# emmc.net
KiCad netlist of a schematic drawn in Altium Designer
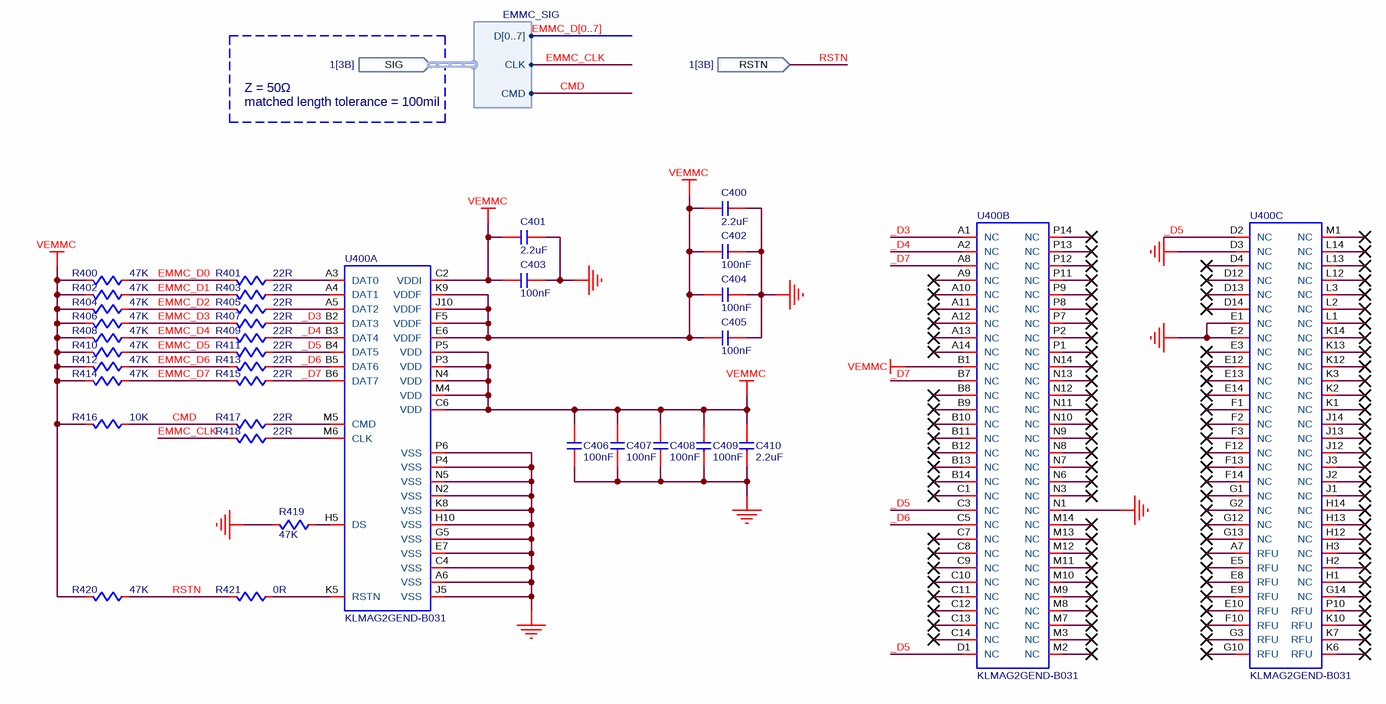
[diagram p0: emmc.schdoc]

(export (version "E")
  (design (tool "Eeschema 10.0.6"))
  (components
    (comp (ref "C400")
      (value "2.2uF")
      (footprint "mw:C0402")
      (fields (field (name "VOLTAGE") "25V") (field (name "Comment") "C-NOMO"))
      (libsource (lib "mw") (part "C-NOMO"))
    )
    (comp (ref "C401")
      (value "2.2uF")
      (footprint "mw:C0402")
      (fields (field (name "VOLTAGE") "25V") (field (name "Comment") "C-NOMO"))
      (libsource (lib "mw") (part "C-NOMO"))
    )
    (comp (ref "C402")
      (value "100nF")
      (footprint "mw:C0402")
      (fields (field (name "VOLTAGE") "25V") (field (name "Comment") "C-NOMO"))
      (libsource (lib "mw") (part "C-NOMO"))
    )
    (comp (ref "C403")
      (value "100nF")
      (footprint "mw:C0402")
      (fields (field (name "VOLTAGE") "25V") (field (name "Comment") "C-NOMO"))
      (libsource (lib "mw") (part "C-NOMO"))
    )
    (comp (ref "C404")
      (value "100nF")
      (footprint "mw:C0402")
      (fields (field (name "VOLTAGE") "25V") (field (name "Comment") "C-NOMO"))
      (libsource (lib "mw") (part "C-NOMO"))
    )
    (comp (ref "C405")
      (value "100nF")
      (footprint "mw:C0402")
      (fields (field (name "VOLTAGE") "25V") (field (name "Comment") "C-NOMO"))
      (libsource (lib "mw") (part "C-NOMO"))
    )
    (comp (ref "C406")
      (value "100nF")
      (footprint "mw:C0402")
      (fields (field (name "VOLTAGE") "25V") (field (name "Comment") "C-NOMO"))
      (libsource (lib "mw") (part "C-NOMO"))
    )
    (comp (ref "C407")
      (value "100nF")
      (footprint "mw:C0402")
      (fields (field (name "VOLTAGE") "25V") (field (name "Comment") "C-NOMO"))
      (libsource (lib "mw") (part "C-NOMO"))
    )
    (comp (ref "C408")
      (value "100nF")
      (footprint "mw:C0402")
      (fields (field (name "VOLTAGE") "25V") (field (name "Comment") "C-NOMO"))
      (libsource (lib "mw") (part "C-NOMO"))
    )
    (comp (ref "C409")
      (value "100nF")
      (footprint "mw:C0402")
      (fields (field (name "VOLTAGE") "25V") (field (name "Comment") "C-NOMO"))
      (libsource (lib "mw") (part "C-NOMO"))
    )
    (comp (ref "C410")
      (value "2.2uF")
      (footprint "mw:C0402")
      (fields (field (name "VOLTAGE") "25V") (field (name "Comment") "C-NOMO"))
      (libsource (lib "mw") (part "C-NOMO"))
    )
    (comp (ref "R400")
      (value "47K")
      (footprint "mw:R0402")
      (fields (field (name "Comment") "R"))
      (libsource (lib "mw") (part "R"))
    )
    (comp (ref "R401")
      (value "22R")
      (footprint "mw:R0402")
      (fields (field (name "Comment") "R"))
      (libsource (lib "mw") (part "R"))
    )
    (comp (ref "R402")
      (value "47K")
      (footprint "mw:R0402")
      (fields (field (name "Comment") "R"))
      (libsource (lib "mw") (part "R"))
    )
    (comp (ref "R403")
      (value "22R")
      (footprint "mw:R0402")
      (fields (field (name "Comment") "R"))
      (libsource (lib "mw") (part "R"))
    )
    (comp (ref "R404")
      (value "47K")
      (footprint "mw:R0402")
      (fields (field (name "Comment") "R"))
      (libsource (lib "mw") (part "R"))
    )
    (comp (ref "R405")
      (value "22R")
      (footprint "mw:R0402")
      (fields (field (name "Comment") "R"))
      (libsource (lib "mw") (part "R"))
    )
    (comp (ref "R406")
      (value "47K")
      (footprint "mw:R0402")
      (fields (field (name "Comment") "R"))
      (libsource (lib "mw") (part "R"))
    )
    (comp (ref "R407")
      (value "22R")
      (footprint "mw:R0402")
      (fields (field (name "Comment") "R"))
      (libsource (lib "mw") (part "R"))
    )
    (comp (ref "R408")
      (value "47K")
      (footprint "mw:R0402")
      (fields (field (name "Comment") "R"))
      (libsource (lib "mw") (part "R"))
    )
    (comp (ref "R409")
      (value "22R")
      (footprint "mw:R0402")
      (fields (field (name "Comment") "R"))
      (libsource (lib "mw") (part "R"))
    )
    (comp (ref "R410")
      (value "47K")
      (footprint "mw:R0402")
      (fields (field (name "Comment") "R"))
      (libsource (lib "mw") (part "R"))
    )
    (comp (ref "R411")
      (value "22R")
      (footprint "mw:R0402")
      (fields (field (name "Comment") "R"))
      (libsource (lib "mw") (part "R"))
    )
    (comp (ref "R412")
      (value "47K")
      (footprint "mw:R0402")
      (fields (field (name "Comment") "R"))
      (libsource (lib "mw") (part "R"))
    )
    (comp (ref "R413")
      (value "22R")
      (footprint "mw:R0402")
      (fields (field (name "Comment") "R"))
      (libsource (lib "mw") (part "R"))
    )
    (comp (ref "R414")
      (value "47K")
      (footprint "mw:R0402")
      (fields (field (name "Comment") "R"))
      (libsource (lib "mw") (part "R"))
    )
    (comp (ref "R415")
      (value "22R")
      (footprint "mw:R0402")
      (fields (field (name "Comment") "R"))
      (libsource (lib "mw") (part "R"))
    )
    (comp (ref "R416")
      (value "10K")
      (footprint "mw:R0402")
      (fields (field (name "Comment") "R"))
      (libsource (lib "mw") (part "R"))
    )
    (comp (ref "R417")
      (value "22R")
      (footprint "mw:R0402")
      (fields (field (name "Comment") "R"))
      (libsource (lib "mw") (part "R"))
    )
    (comp (ref "R418")
      (value "22R")
      (footprint "mw:R0402")
      (fields (field (name "Comment") "R"))
      (libsource (lib "mw") (part "R"))
    )
    (comp (ref "R419")
      (value "47K")
      (footprint "mw:R0402")
      (fields (field (name "Comment") "R"))
      (libsource (lib "mw") (part "R"))
    )
    (comp (ref "R420")
      (value "47K")
      (footprint "mw:R0402")
      (fields (field (name "Comment") "R"))
      (libsource (lib "mw") (part "R"))
    )
    (comp (ref "R421")
      (value "0R")
      (footprint "mw:R0402")
      (fields (field (name "Comment") "R"))
      (libsource (lib "mw") (part "R"))
    )
    (comp (ref "U400")
      (value "KLMAG2GEND-B031")
      (footprint "mw:KLMAG2GEND-B031")
      (description "EMMC")
      (libsource (lib "mw") (part "KLMAG2GEND-B031"))
    )
  )
  (nets
    (net (code "2") (name "/CMD") (class "Default")
      (node (ref "R416") (pin "2") (pinfunction "2_2") (pintype "passive"))
      (node (ref "R417") (pin "1") (pinfunction "1_1") (pintype "passive"))
    )
    (net (code "3") (name "/EMMC_CLK") (class "Default")
      (node (ref "R418") (pin "1") (pinfunction "1_1") (pintype "passive"))
    )
    (net (code "4") (name "/EMMC_D0") (class "Default")
      (node (ref "R400") (pin "2") (pinfunction "2_2") (pintype "passive"))
      (node (ref "R401") (pin "1") (pinfunction "1_1") (pintype "passive"))
    )
    (net (code "5") (name "/EMMC_D1") (class "Default")
      (node (ref "R402") (pin "2") (pinfunction "2_2") (pintype "passive"))
      (node (ref "R403") (pin "1") (pinfunction "1_1") (pintype "passive"))
    )
    (net (code "6") (name "/EMMC_D2") (class "Default")
      (node (ref "R404") (pin "2") (pinfunction "2_2") (pintype "passive"))
      (node (ref "R405") (pin "1") (pinfunction "1_1") (pintype "passive"))
    )
    (net (code "7") (name "/EMMC_D3") (class "Default")
      (node (ref "R406") (pin "2") (pinfunction "2_2") (pintype "passive"))
      (node (ref "R407") (pin "1") (pinfunction "1_1") (pintype "passive"))
    )
    (net (code "8") (name "/EMMC_D4") (class "Default")
      (node (ref "R408") (pin "2") (pinfunction "2_2") (pintype "passive"))
      (node (ref "R409") (pin "1") (pinfunction "1_1") (pintype "passive"))
    )
    (net (code "9") (name "/EMMC_D5") (class "Default")
      (node (ref "R410") (pin "2") (pinfunction "2_2") (pintype "passive"))
      (node (ref "R411") (pin "1") (pinfunction "1_1") (pintype "passive"))
    )
    (net (code "10") (name "/EMMC_D6") (class "Default")
      (node (ref "R412") (pin "2") (pinfunction "2_2") (pintype "passive"))
      (node (ref "R413") (pin "1") (pinfunction "1_1") (pintype "passive"))
    )
    (net (code "11") (name "/EMMC_D7") (class "Default")
      (node (ref "R414") (pin "2") (pinfunction "2_2") (pintype "passive"))
      (node (ref "R415") (pin "1") (pinfunction "1_1") (pintype "passive"))
    )
    (net (code "13") (name "/RSTN") (class "Default")
      (node (ref "R420") (pin "2") (pinfunction "2_2") (pintype "passive"))
      (node (ref "R421") (pin "1") (pinfunction "1_1") (pintype "passive"))
    )
    (net (code "14") (name "/_D3") (class "Default")
      (node (ref "R407") (pin "2") (pinfunction "2_2") (pintype "passive"))
      (node (ref "U400") (pin "A1") (pinfunction "NC_A1") (pintype "passive"))
      (node (ref "U400") (pin "B2") (pinfunction "DAT3_B2") (pintype "passive"))
    )
    (net (code "15") (name "/_D4") (class "Default")
      (node (ref "R409") (pin "2") (pinfunction "2_2") (pintype "passive"))
      (node (ref "U400") (pin "A2") (pinfunction "NC_A2") (pintype "passive"))
      (node (ref "U400") (pin "B3") (pinfunction "DAT4_B3") (pintype "passive"))
    )
    (net (code "16") (name "/_D5") (class "Default")
      (node (ref "R411") (pin "2") (pinfunction "2_2") (pintype "passive"))
      (node (ref "U400") (pin "B4") (pinfunction "DAT5_B4") (pintype "passive"))
      (node (ref "U400") (pin "C3") (pinfunction "NC_C3") (pintype "passive"))
      (node (ref "U400") (pin "D1") (pinfunction "NC_D1") (pintype "passive"))
      (node (ref "U400") (pin "D2") (pinfunction "NC_D2") (pintype "passive"))
    )
    (net (code "17") (name "/_D6") (class "Default")
      (node (ref "R413") (pin "2") (pinfunction "2_2") (pintype "passive"))
      (node (ref "U400") (pin "B5") (pinfunction "DAT6_B5") (pintype "passive"))
      (node (ref "U400") (pin "C5") (pinfunction "NC_C5") (pintype "passive"))
    )
    (net (code "18") (name "/_D7") (class "Default")
      (node (ref "R415") (pin "2") (pinfunction "2_2") (pintype "passive"))
      (node (ref "U400") (pin "A8") (pinfunction "NC_A8") (pintype "passive"))
      (node (ref "U400") (pin "B6") (pinfunction "DAT7_B6") (pintype "passive"))
      (node (ref "U400") (pin "B7") (pinfunction "NC_B7") (pintype "passive"))
    )
    (net (code "20") (name "GND") (class "Default")
      (node (ref "C400") (pin "1") (pinfunction "1_1") (pintype "passive"))
      (node (ref "C401") (pin "1") (pinfunction "1_1") (pintype "passive"))
      (node (ref "C402") (pin "1") (pinfunction "1_1") (pintype "passive"))
      (node (ref "C403") (pin "1") (pinfunction "1_1") (pintype "passive"))
      (node (ref "C404") (pin "1") (pinfunction "1_1") (pintype "passive"))
      (node (ref "C405") (pin "1") (pinfunction "1_1") (pintype "passive"))
      (node (ref "C406") (pin "1") (pinfunction "1_1") (pintype "passive"))
      (node (ref "C407") (pin "1") (pinfunction "1_1") (pintype "passive"))
      (node (ref "C408") (pin "1") (pinfunction "1_1") (pintype "passive"))
      (node (ref "C409") (pin "1") (pinfunction "1_1") (pintype "passive"))
      (node (ref "C410") (pin "1") (pinfunction "1_1") (pintype "passive"))
      (node (ref "R419") (pin "1") (pinfunction "1_1") (pintype "passive"))
      (node (ref "U400") (pin "A6") (pinfunction "VSS_A6") (pintype "passive"))
      (node (ref "U400") (pin "C4") (pinfunction "VSS_C4") (pintype "passive"))
      (node (ref "U400") (pin "D3") (pinfunction "NC_D3") (pintype "passive"))
      (node (ref "U400") (pin "E1") (pinfunction "NC_E1") (pintype "passive"))
      (node (ref "U400") (pin "E2") (pinfunction "NC_E2") (pintype "passive"))
      (node (ref "U400") (pin "E7") (pinfunction "VSS_E7") (pintype "passive"))
      (node (ref "U400") (pin "G5") (pinfunction "VSS_G5") (pintype "passive"))
      (node (ref "U400") (pin "H10") (pinfunction "VSS_H10") (pintype "passive"))
      (node (ref "U400") (pin "J5") (pinfunction "VSS_J5") (pintype "passive"))
      (node (ref "U400") (pin "K8") (pinfunction "VSS_K8") (pintype "passive"))
      (node (ref "U400") (pin "N1") (pinfunction "NC_N1") (pintype "passive"))
      (node (ref "U400") (pin "N2") (pinfunction "VSS_N2") (pintype "passive"))
      (node (ref "U400") (pin "N5") (pinfunction "VSS_N5") (pintype "passive"))
      (node (ref "U400") (pin "P4") (pinfunction "VSS_P4") (pintype "passive"))
      (node (ref "U400") (pin "P6") (pinfunction "VSS_P6") (pintype "passive"))
    )
    (net (code "21") (name "Net-(U400A-CLK)") (class "Default")
      (node (ref "R418") (pin "2") (pinfunction "2_2") (pintype "passive"))
      (node (ref "U400") (pin "M6") (pinfunction "CLK_M6") (pintype "passive"))
    )
    (net (code "22") (name "Net-(U400A-CMD)") (class "Default")
      (node (ref "R417") (pin "2") (pinfunction "2_2") (pintype "passive"))
      (node (ref "U400") (pin "M5") (pinfunction "CMD_M5") (pintype "passive"))
    )
    (net (code "23") (name "Net-(U400A-DAT0)") (class "Default")
      (node (ref "R401") (pin "2") (pinfunction "2_2") (pintype "passive"))
      (node (ref "U400") (pin "A3") (pinfunction "DAT0_A3") (pintype "passive"))
    )
    (net (code "24") (name "Net-(U400A-DAT1)") (class "Default")
      (node (ref "R403") (pin "2") (pinfunction "2_2") (pintype "passive"))
      (node (ref "U400") (pin "A4") (pinfunction "DAT1_A4") (pintype "passive"))
    )
    (net (code "25") (name "Net-(U400A-DAT2)") (class "Default")
      (node (ref "R405") (pin "2") (pinfunction "2_2") (pintype "passive"))
      (node (ref "U400") (pin "A5") (pinfunction "DAT2_A5") (pintype "passive"))
    )
    (net (code "26") (name "Net-(U400A-DS)") (class "Default")
      (node (ref "R419") (pin "2") (pinfunction "2_2") (pintype "passive"))
      (node (ref "U400") (pin "H5") (pinfunction "DS_H5") (pintype "passive"))
    )
    (net (code "27") (name "Net-(U400A-RSTN)") (class "Default")
      (node (ref "R421") (pin "2") (pinfunction "2_2") (pintype "passive"))
      (node (ref "U400") (pin "K5") (pinfunction "RSTN_K5") (pintype "passive"))
    )
    (net (code "28") (name "VEMMC") (class "Default")
      (node (ref "C400") (pin "2") (pinfunction "2_2") (pintype "passive"))
      (node (ref "C401") (pin "2") (pinfunction "2_2") (pintype "passive"))
      (node (ref "C402") (pin "2") (pinfunction "2_2") (pintype "passive"))
      (node (ref "C403") (pin "2") (pinfunction "2_2") (pintype "passive"))
      (node (ref "C404") (pin "2") (pinfunction "2_2") (pintype "passive"))
      (node (ref "C405") (pin "2") (pinfunction "2_2") (pintype "passive"))
      (node (ref "C406") (pin "2") (pinfunction "2_2") (pintype "passive"))
      (node (ref "C407") (pin "2") (pinfunction "2_2") (pintype "passive"))
      (node (ref "C408") (pin "2") (pinfunction "2_2") (pintype "passive"))
      (node (ref "C409") (pin "2") (pinfunction "2_2") (pintype "passive"))
      (node (ref "C410") (pin "2") (pinfunction "2_2") (pintype "passive"))
      (node (ref "R400") (pin "1") (pinfunction "1_1") (pintype "passive"))
      (node (ref "R402") (pin "1") (pinfunction "1_1") (pintype "passive"))
      (node (ref "R404") (pin "1") (pinfunction "1_1") (pintype "passive"))
      (node (ref "R406") (pin "1") (pinfunction "1_1") (pintype "passive"))
      (node (ref "R408") (pin "1") (pinfunction "1_1") (pintype "passive"))
      (node (ref "R410") (pin "1") (pinfunction "1_1") (pintype "passive"))
      (node (ref "R412") (pin "1") (pinfunction "1_1") (pintype "passive"))
      (node (ref "R414") (pin "1") (pinfunction "1_1") (pintype "passive"))
      (node (ref "R416") (pin "1") (pinfunction "1_1") (pintype "passive"))
      (node (ref "R420") (pin "1") (pinfunction "1_1") (pintype "passive"))
      (node (ref "U400") (pin "B1") (pinfunction "NC_B1") (pintype "passive"))
      (node (ref "U400") (pin "C2") (pinfunction "VDDI_C2") (pintype "passive"))
      (node (ref "U400") (pin "C6") (pinfunction "VDD_C6") (pintype "passive"))
      (node (ref "U400") (pin "E6") (pinfunction "VDDF_E6") (pintype "passive"))
      (node (ref "U400") (pin "F5") (pinfunction "VDDF_F5") (pintype "passive"))
      (node (ref "U400") (pin "J10") (pinfunction "VDDF_J10") (pintype "passive"))
      (node (ref "U400") (pin "K9") (pinfunction "VDDF_K9") (pintype "passive"))
      (node (ref "U400") (pin "M4") (pinfunction "VDD_M4") (pintype "passive"))
      (node (ref "U400") (pin "N4") (pinfunction "VDD_N4") (pintype "passive"))
      (node (ref "U400") (pin "P3") (pinfunction "VDD_P3") (pintype "passive"))
      (node (ref "U400") (pin "P5") (pinfunction "VDD_P5") (pintype "passive"))
    )
    (net (code "29") (name "unconnected-(U400B-NC-PadA9)") (class "Default")
      (node (ref "U400") (pin "A9") (pinfunction "NC_A9") (pintype "passive+no_connect"))
    )
    (net (code "30") (name "unconnected-(U400B-NC-PadA10)") (class "Default")
      (node (ref "U400") (pin "A10") (pinfunction "NC_A10") (pintype "passive+no_connect"))
    )
    (net (code "31") (name "unconnected-(U400B-NC-PadA11)") (class "Default")
      (node (ref "U400") (pin "A11") (pinfunction "NC_A11") (pintype "passive+no_connect"))
    )
    (net (code "32") (name "unconnected-(U400B-NC-PadA12)") (class "Default")
      (node (ref "U400") (pin "A12") (pinfunction "NC_A12") (pintype "passive+no_connect"))
    )
    (net (code "33") (name "unconnected-(U400B-NC-PadA13)") (class "Default")
      (node (ref "U400") (pin "A13") (pinfunction "NC_A13") (pintype "passive+no_connect"))
    )
    (net (code "34") (name "unconnected-(U400B-NC-PadA14)") (class "Default")
      (node (ref "U400") (pin "A14") (pinfunction "NC_A14") (pintype "passive+no_connect"))
    )
    (net (code "35") (name "unconnected-(U400B-NC-PadB8)") (class "Default")
      (node (ref "U400") (pin "B8") (pinfunction "NC_B8") (pintype "passive+no_connect"))
    )
    (net (code "36") (name "unconnected-(U400B-NC-PadB9)") (class "Default")
      (node (ref "U400") (pin "B9") (pinfunction "NC_B9") (pintype "passive+no_connect"))
    )
    (net (code "37") (name "unconnected-(U400B-NC-PadB10)") (class "Default")
      (node (ref "U400") (pin "B10") (pinfunction "NC_B10") (pintype "passive+no_connect"))
    )
    (net (code "38") (name "unconnected-(U400B-NC-PadB11)") (class "Default")
      (node (ref "U400") (pin "B11") (pinfunction "NC_B11") (pintype "passive+no_connect"))
    )
    (net (code "39") (name "unconnected-(U400B-NC-PadB12)") (class "Default")
      (node (ref "U400") (pin "B12") (pinfunction "NC_B12") (pintype "passive+no_connect"))
    )
    (net (code "40") (name "unconnected-(U400B-NC-PadB13)") (class "Default")
      (node (ref "U400") (pin "B13") (pinfunction "NC_B13") (pintype "passive+no_connect"))
    )
    (net (code "41") (name "unconnected-(U400B-NC-PadB14)") (class "Default")
      (node (ref "U400") (pin "B14") (pinfunction "NC_B14") (pintype "passive+no_connect"))
    )
    (net (code "42") (name "unconnected-(U400B-NC-PadC1)") (class "Default")
      (node (ref "U400") (pin "C1") (pinfunction "NC_C1") (pintype "passive+no_connect"))
    )
    (net (code "43") (name "unconnected-(U400B-NC-PadC7)") (class "Default")
      (node (ref "U400") (pin "C7") (pinfunction "NC_C7") (pintype "passive+no_connect"))
    )
    (net (code "44") (name "unconnected-(U400B-NC-PadC8)") (class "Default")
      (node (ref "U400") (pin "C8") (pinfunction "NC_C8") (pintype "passive+no_connect"))
    )
    (net (code "45") (name "unconnected-(U400B-NC-PadC9)") (class "Default")
      (node (ref "U400") (pin "C9") (pinfunction "NC_C9") (pintype "passive+no_connect"))
    )
    (net (code "46") (name "unconnected-(U400B-NC-PadC10)") (class "Default")
      (node (ref "U400") (pin "C10") (pinfunction "NC_C10") (pintype "passive+no_connect"))
    )
    (net (code "47") (name "unconnected-(U400B-NC-PadC11)") (class "Default")
      (node (ref "U400") (pin "C11") (pinfunction "NC_C11") (pintype "passive+no_connect"))
    )
    (net (code "48") (name "unconnected-(U400B-NC-PadC12)") (class "Default")
      (node (ref "U400") (pin "C12") (pinfunction "NC_C12") (pintype "passive+no_connect"))
    )
    (net (code "49") (name "unconnected-(U400B-NC-PadC13)") (class "Default")
      (node (ref "U400") (pin "C13") (pinfunction "NC_C13") (pintype "passive+no_connect"))
    )
    (net (code "50") (name "unconnected-(U400B-NC-PadC14)") (class "Default")
      (node (ref "U400") (pin "C14") (pinfunction "NC_C14") (pintype "passive+no_connect"))
    )
    (net (code "51") (name "unconnected-(U400B-NC-PadM2)") (class "Default")
      (node (ref "U400") (pin "M2") (pinfunction "NC_M2") (pintype "passive+no_connect"))
    )
    (net (code "52") (name "unconnected-(U400B-NC-PadM3)") (class "Default")
      (node (ref "U400") (pin "M3") (pinfunction "NC_M3") (pintype "passive+no_connect"))
    )
    (net (code "53") (name "unconnected-(U400B-NC-PadM7)") (class "Default")
      (node (ref "U400") (pin "M7") (pinfunction "NC_M7") (pintype "passive+no_connect"))
    )
    (net (code "54") (name "unconnected-(U400B-NC-PadM8)") (class "Default")
      (node (ref "U400") (pin "M8") (pinfunction "NC_M8") (pintype "passive+no_connect"))
    )
    (net (code "55") (name "unconnected-(U400B-NC-PadM9)") (class "Default")
      (node (ref "U400") (pin "M9") (pinfunction "NC_M9") (pintype "passive+no_connect"))
    )
    (net (code "56") (name "unconnected-(U400B-NC-PadM10)") (class "Default")
      (node (ref "U400") (pin "M10") (pinfunction "NC_M10") (pintype "passive+no_connect"))
    )
    (net (code "57") (name "unconnected-(U400B-NC-PadM11)") (class "Default")
      (node (ref "U400") (pin "M11") (pinfunction "NC_M11") (pintype "passive+no_connect"))
    )
    (net (code "58") (name "unconnected-(U400B-NC-PadM12)") (class "Default")
      (node (ref "U400") (pin "M12") (pinfunction "NC_M12") (pintype "passive+no_connect"))
    )
    (net (code "59") (name "unconnected-(U400B-NC-PadM13)") (class "Default")
      (node (ref "U400") (pin "M13") (pinfunction "NC_M13") (pintype "passive+no_connect"))
    )
    (net (code "60") (name "unconnected-(U400B-NC-PadM14)") (class "Default")
      (node (ref "U400") (pin "M14") (pinfunction "NC_M14") (pintype "passive+no_connect"))
    )
    (net (code "61") (name "unconnected-(U400B-NC-PadN3)") (class "Default")
      (node (ref "U400") (pin "N3") (pinfunction "NC_N3") (pintype "passive+no_connect"))
    )
    (net (code "62") (name "unconnected-(U400B-NC-PadN6)") (class "Default")
      (node (ref "U400") (pin "N6") (pinfunction "NC_N6") (pintype "passive+no_connect"))
    )
    (net (code "63") (name "unconnected-(U400B-NC-PadN7)") (class "Default")
      (node (ref "U400") (pin "N7") (pinfunction "NC_N7") (pintype "passive+no_connect"))
    )
    (net (code "64") (name "unconnected-(U400B-NC-PadN8)") (class "Default")
      (node (ref "U400") (pin "N8") (pinfunction "NC_N8") (pintype "passive+no_connect"))
    )
    (net (code "65") (name "unconnected-(U400B-NC-PadN9)") (class "Default")
      (node (ref "U400") (pin "N9") (pinfunction "NC_N9") (pintype "passive+no_connect"))
    )
    (net (code "66") (name "unconnected-(U400B-NC-PadN10)") (class "Default")
      (node (ref "U400") (pin "N10") (pinfunction "NC_N10") (pintype "passive+no_connect"))
    )
    (net (code "67") (name "unconnected-(U400B-NC-PadN11)") (class "Default")
      (node (ref "U400") (pin "N11") (pinfunction "NC_N11") (pintype "passive+no_connect"))
    )
    (net (code "68") (name "unconnected-(U400B-NC-PadN12)") (class "Default")
      (node (ref "U400") (pin "N12") (pinfunction "NC_N12") (pintype "passive+no_connect"))
    )
    (net (code "69") (name "unconnected-(U400B-NC-PadN13)") (class "Default")
      (node (ref "U400") (pin "N13") (pinfunction "NC_N13") (pintype "passive+no_connect"))
    )
    (net (code "70") (name "unconnected-(U400B-NC-PadN14)") (class "Default")
      (node (ref "U400") (pin "N14") (pinfunction "NC_N14") (pintype "passive+no_connect"))
    )
    (net (code "71") (name "unconnected-(U400B-NC-PadP1)") (class "Default")
      (node (ref "U400") (pin "P1") (pinfunction "NC_P1") (pintype "passive+no_connect"))
    )
    (net (code "72") (name "unconnected-(U400B-NC-PadP2)") (class "Default")
      (node (ref "U400") (pin "P2") (pinfunction "NC_P2") (pintype "passive+no_connect"))
    )
    (net (code "73") (name "unconnected-(U400B-NC-PadP7)") (class "Default")
      (node (ref "U400") (pin "P7") (pinfunction "NC_P7") (pintype "passive+no_connect"))
    )
    (net (code "74") (name "unconnected-(U400B-NC-PadP8)") (class "Default")
      (node (ref "U400") (pin "P8") (pinfunction "NC_P8") (pintype "passive+no_connect"))
    )
    (net (code "75") (name "unconnected-(U400B-NC-PadP9)") (class "Default")
      (node (ref "U400") (pin "P9") (pinfunction "NC_P9") (pintype "passive+no_connect"))
    )
    (net (code "76") (name "unconnected-(U400B-NC-PadP11)") (class "Default")
      (node (ref "U400") (pin "P11") (pinfunction "NC_P11") (pintype "passive+no_connect"))
    )
    (net (code "77") (name "unconnected-(U400B-NC-PadP12)") (class "Default")
      (node (ref "U400") (pin "P12") (pinfunction "NC_P12") (pintype "passive+no_connect"))
    )
    (net (code "78") (name "unconnected-(U400B-NC-PadP13)") (class "Default")
      (node (ref "U400") (pin "P13") (pinfunction "NC_P13") (pintype "passive+no_connect"))
    )
    (net (code "79") (name "unconnected-(U400B-NC-PadP14)") (class "Default")
      (node (ref "U400") (pin "P14") (pinfunction "NC_P14") (pintype "passive+no_connect"))
    )
    (net (code "80") (name "unconnected-(U400C-NC-PadD4)") (class "Default")
      (node (ref "U400") (pin "D4") (pinfunction "NC_D4") (pintype "passive+no_connect"))
    )
    (net (code "81") (name "unconnected-(U400C-NC-PadD12)") (class "Default")
      (node (ref "U400") (pin "D12") (pinfunction "NC_D12") (pintype "passive+no_connect"))
    )
    (net (code "82") (name "unconnected-(U400C-NC-PadD13)") (class "Default")
      (node (ref "U400") (pin "D13") (pinfunction "NC_D13") (pintype "passive+no_connect"))
    )
    (net (code "83") (name "unconnected-(U400C-NC-PadD14)") (class "Default")
      (node (ref "U400") (pin "D14") (pinfunction "NC_D14") (pintype "passive+no_connect"))
    )
    (net (code "84") (name "unconnected-(U400C-NC-PadE3)") (class "Default")
      (node (ref "U400") (pin "E3") (pinfunction "NC_E3") (pintype "passive+no_connect"))
    )
    (net (code "85") (name "unconnected-(U400C-NC-PadE12)") (class "Default")
      (node (ref "U400") (pin "E12") (pinfunction "NC_E12") (pintype "passive+no_connect"))
    )
    (net (code "86") (name "unconnected-(U400C-NC-PadE13)") (class "Default")
      (node (ref "U400") (pin "E13") (pinfunction "NC_E13") (pintype "passive+no_connect"))
    )
    (net (code "87") (name "unconnected-(U400C-NC-PadE14)") (class "Default")
      (node (ref "U400") (pin "E14") (pinfunction "NC_E14") (pintype "passive+no_connect"))
    )
    (net (code "88") (name "unconnected-(U400C-NC-PadF1)") (class "Default")
      (node (ref "U400") (pin "F1") (pinfunction "NC_F1") (pintype "passive+no_connect"))
    )
    (net (code "89") (name "unconnected-(U400C-NC-PadF2)") (class "Default")
      (node (ref "U400") (pin "F2") (pinfunction "NC_F2") (pintype "passive+no_connect"))
    )
    (net (code "90") (name "unconnected-(U400C-NC-PadF3)") (class "Default")
      (node (ref "U400") (pin "F3") (pinfunction "NC_F3") (pintype "passive+no_connect"))
    )
    (net (code "91") (name "unconnected-(U400C-NC-PadF12)") (class "Default")
      (node (ref "U400") (pin "F12") (pinfunction "NC_F12") (pintype "passive+no_connect"))
    )
    (net (code "92") (name "unconnected-(U400C-NC-PadF13)") (class "Default")
      (node (ref "U400") (pin "F13") (pinfunction "NC_F13") (pintype "passive+no_connect"))
    )
    (net (code "93") (name "unconnected-(U400C-NC-PadF14)") (class "Default")
      (node (ref "U400") (pin "F14") (pinfunction "NC_F14") (pintype "passive+no_connect"))
    )
    (net (code "94") (name "unconnected-(U400C-NC-PadG1)") (class "Default")
      (node (ref "U400") (pin "G1") (pinfunction "NC_G1") (pintype "passive+no_connect"))
    )
    (net (code "95") (name "unconnected-(U400C-NC-PadG2)") (class "Default")
      (node (ref "U400") (pin "G2") (pinfunction "NC_G2") (pintype "passive+no_connect"))
    )
    (net (code "96") (name "unconnected-(U400C-NC-PadG12)") (class "Default")
      (node (ref "U400") (pin "G12") (pinfunction "NC_G12") (pintype "passive+no_connect"))
    )
    (net (code "97") (name "unconnected-(U400C-NC-PadG13)") (class "Default")
      (node (ref "U400") (pin "G13") (pinfunction "NC_G13") (pintype "passive+no_connect"))
    )
    (net (code "98") (name "unconnected-(U400C-NC-PadG14)") (class "Default")
      (node (ref "U400") (pin "G14") (pinfunction "NC_G14") (pintype "passive+no_connect"))
    )
    (net (code "99") (name "unconnected-(U400C-NC-PadH1)") (class "Default")
      (node (ref "U400") (pin "H1") (pinfunction "NC_H1") (pintype "passive+no_connect"))
    )
    (net (code "100") (name "unconnected-(U400C-NC-PadH2)") (class "Default")
      (node (ref "U400") (pin "H2") (pinfunction "NC_H2") (pintype "passive+no_connect"))
    )
    (net (code "101") (name "unconnected-(U400C-NC-PadH3)") (class "Default")
      (node (ref "U400") (pin "H3") (pinfunction "NC_H3") (pintype "passive+no_connect"))
    )
    (net (code "102") (name "unconnected-(U400C-NC-PadH12)") (class "Default")
      (node (ref "U400") (pin "H12") (pinfunction "NC_H12") (pintype "passive+no_connect"))
    )
    (net (code "103") (name "unconnected-(U400C-NC-PadH13)") (class "Default")
      (node (ref "U400") (pin "H13") (pinfunction "NC_H13") (pintype "passive+no_connect"))
    )
    (net (code "104") (name "unconnected-(U400C-NC-PadH14)") (class "Default")
      (node (ref "U400") (pin "H14") (pinfunction "NC_H14") (pintype "passive+no_connect"))
    )
    (net (code "105") (name "unconnected-(U400C-NC-PadJ1)") (class "Default")
      (node (ref "U400") (pin "J1") (pinfunction "NC_J1") (pintype "passive+no_connect"))
    )
    (net (code "106") (name "unconnected-(U400C-NC-PadJ2)") (class "Default")
      (node (ref "U400") (pin "J2") (pinfunction "NC_J2") (pintype "passive+no_connect"))
    )
    (net (code "107") (name "unconnected-(U400C-NC-PadJ3)") (class "Default")
      (node (ref "U400") (pin "J3") (pinfunction "NC_J3") (pintype "passive+no_connect"))
    )
    (net (code "108") (name "unconnected-(U400C-NC-PadJ12)") (class "Default")
      (node (ref "U400") (pin "J12") (pinfunction "NC_J12") (pintype "passive+no_connect"))
    )
    (net (code "109") (name "unconnected-(U400C-NC-PadJ13)") (class "Default")
      (node (ref "U400") (pin "J13") (pinfunction "NC_J13") (pintype "passive+no_connect"))
    )
    (net (code "110") (name "unconnected-(U400C-NC-PadJ14)") (class "Default")
      (node (ref "U400") (pin "J14") (pinfunction "NC_J14") (pintype "passive+no_connect"))
    )
    (net (code "111") (name "unconnected-(U400C-NC-PadK1)") (class "Default")
      (node (ref "U400") (pin "K1") (pinfunction "NC_K1") (pintype "passive+no_connect"))
    )
    (net (code "112") (name "unconnected-(U400C-NC-PadK2)") (class "Default")
      (node (ref "U400") (pin "K2") (pinfunction "NC_K2") (pintype "passive+no_connect"))
    )
    (net (code "113") (name "unconnected-(U400C-NC-PadK3)") (class "Default")
      (node (ref "U400") (pin "K3") (pinfunction "NC_K3") (pintype "passive+no_connect"))
    )
    (net (code "114") (name "unconnected-(U400C-NC-PadK12)") (class "Default")
      (node (ref "U400") (pin "K12") (pinfunction "NC_K12") (pintype "passive+no_connect"))
    )
    (net (code "115") (name "unconnected-(U400C-NC-PadK13)") (class "Default")
      (node (ref "U400") (pin "K13") (pinfunction "NC_K13") (pintype "passive+no_connect"))
    )
    (net (code "116") (name "unconnected-(U400C-NC-PadK14)") (class "Default")
      (node (ref "U400") (pin "K14") (pinfunction "NC_K14") (pintype "passive+no_connect"))
    )
    (net (code "117") (name "unconnected-(U400C-NC-PadL1)") (class "Default")
      (node (ref "U400") (pin "L1") (pinfunction "NC_L1") (pintype "passive+no_connect"))
    )
    (net (code "118") (name "unconnected-(U400C-NC-PadL2)") (class "Default")
      (node (ref "U400") (pin "L2") (pinfunction "NC_L2") (pintype "passive+no_connect"))
    )
    (net (code "119") (name "unconnected-(U400C-NC-PadL3)") (class "Default")
      (node (ref "U400") (pin "L3") (pinfunction "NC_L3") (pintype "passive+no_connect"))
    )
    (net (code "120") (name "unconnected-(U400C-NC-PadL12)") (class "Default")
      (node (ref "U400") (pin "L12") (pinfunction "NC_L12") (pintype "passive+no_connect"))
    )
    (net (code "121") (name "unconnected-(U400C-NC-PadL13)") (class "Default")
      (node (ref "U400") (pin "L13") (pinfunction "NC_L13") (pintype "passive+no_connect"))
    )
    (net (code "122") (name "unconnected-(U400C-NC-PadL14)") (class "Default")
      (node (ref "U400") (pin "L14") (pinfunction "NC_L14") (pintype "passive+no_connect"))
    )
    (net (code "123") (name "unconnected-(U400C-NC-PadM1)") (class "Default")
      (node (ref "U400") (pin "M1") (pinfunction "NC_M1") (pintype "passive+no_connect"))
    )
    (net (code "124") (name "unconnected-(U400C-RFU-PadA7)") (class "Default")
      (node (ref "U400") (pin "A7") (pinfunction "RFU_A7") (pintype "passive+no_connect"))
    )
    (net (code "125") (name "unconnected-(U400C-RFU-PadE5)") (class "Default")
      (node (ref "U400") (pin "E5") (pinfunction "RFU_E5") (pintype "passive+no_connect"))
    )
    (net (code "126") (name "unconnected-(U400C-RFU-PadE8)") (class "Default")
      (node (ref "U400") (pin "E8") (pinfunction "RFU_E8") (pintype "passive+no_connect"))
    )
    (net (code "127") (name "unconnected-(U400C-RFU-PadE9)") (class "Default")
      (node (ref "U400") (pin "E9") (pinfunction "RFU_E9") (pintype "passive+no_connect"))
    )
    (net (code "128") (name "unconnected-(U400C-RFU-PadE10)") (class "Default")
      (node (ref "U400") (pin "E10") (pinfunction "RFU_E10") (pintype "passive+no_connect"))
    )
    (net (code "129") (name "unconnected-(U400C-RFU-PadF10)") (class "Default")
      (node (ref "U400") (pin "F10") (pinfunction "RFU_F10") (pintype "passive+no_connect"))
    )
    (net (code "130") (name "unconnected-(U400C-RFU-PadG3)") (class "Default")
      (node (ref "U400") (pin "G3") (pinfunction "RFU_G3") (pintype "passive+no_connect"))
    )
    (net (code "131") (name "unconnected-(U400C-RFU-PadG10)") (class "Default")
      (node (ref "U400") (pin "G10") (pinfunction "RFU_G10") (pintype "passive+no_connect"))
    )
    (net (code "132") (name "unconnected-(U400C-RFU-PadK6)") (class "Default")
      (node (ref "U400") (pin "K6") (pinfunction "RFU_K6") (pintype "passive+no_connect"))
    )
    (net (code "133") (name "unconnected-(U400C-RFU-PadK7)") (class "Default")
      (node (ref "U400") (pin "K7") (pinfunction "RFU_K7") (pintype "passive+no_connect"))
    )
    (net (code "134") (name "unconnected-(U400C-RFU-PadK10)") (class "Default")
      (node (ref "U400") (pin "K10") (pinfunction "RFU_K10") (pintype "passive+no_connect"))
    )
    (net (code "135") (name "unconnected-(U400C-RFU-PadP10)") (class "Default")
      (node (ref "U400") (pin "P10") (pinfunction "RFU_P10") (pintype "passive+no_connect"))
    )
  )
)
